# PCF8547.net
KiCad netlist of a schematic drawn in Altium Designer
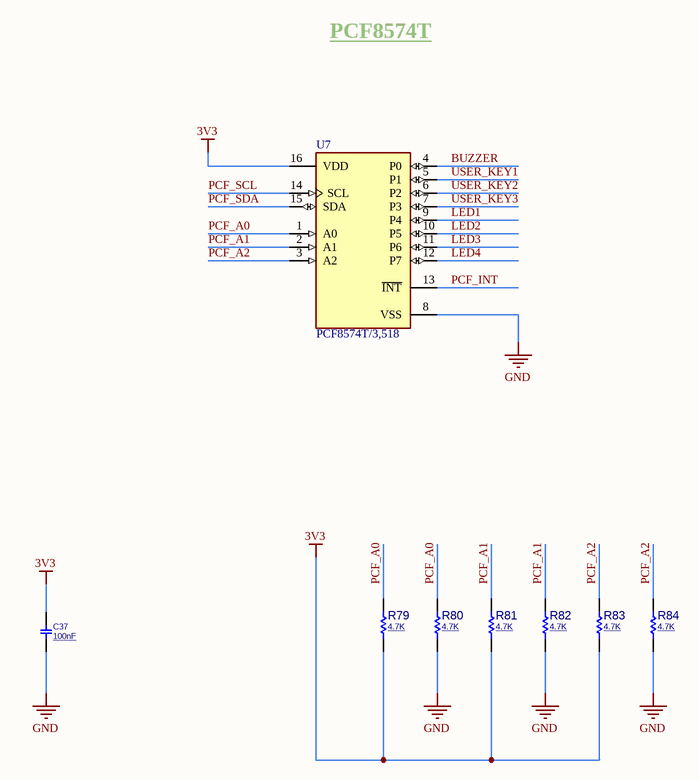
[diagram p0: PCF8547.SchDoc]

(export (version "E")
  (design (tool "Eeschema 10.0.6"))
  (components
    (comp (ref "C37")
      (value "100nF")
      (footprint "C0603")
      (description "CAP, MLCC, -F, -V, MATERIAL, -%, 0201")
      (fields (field (name "MANF_P#") "MANF_PART#"))
      (libsource (lib "passive_smd") (part "CAP_SMD_MLCC_0603"))
    )
    (comp (ref "R79")
      (value "4.7K")
      (footprint "R0603")
      (description "RESISTOR, SMD")
      (libsource (lib "passive_smd") (part "RES_SMD"))
    )
    (comp (ref "R80")
      (value "4.7K")
      (footprint "R0603")
      (description "RESISTOR, SMD")
      (libsource (lib "passive_smd") (part "RES_SMD"))
    )
    (comp (ref "R81")
      (value "4.7K")
      (footprint "R0603")
      (description "RESISTOR, SMD")
      (libsource (lib "passive_smd") (part "RES_SMD"))
    )
    (comp (ref "R82")
      (value "4.7K")
      (footprint "R0603")
      (description "RESISTOR, SMD")
      (libsource (lib "passive_smd") (part "RES_SMD"))
    )
    (comp (ref "R83")
      (value "4.7K")
      (footprint "R0603")
      (description "RESISTOR, SMD")
      (libsource (lib "passive_smd") (part "RES_SMD"))
    )
    (comp (ref "R84")
      (value "4.7K")
      (footprint "R0603")
      (description "RESISTOR, SMD")
      (libsource (lib "passive_smd") (part "RES_SMD"))
    )
    (comp (ref "U7")
      (value "PCF8574T/3,518")
      (footprint "FP-SOT162-1-MFG")
      (description "IC I/O EXPANDER I2C 8B 16SOIC")
      (fields
        (field (name "MANUFACTURER") "NXP Semiconductors")
        (field (name "OCTOPART") "https://octopart.com/pcf8574t%2F3%2C518-nxp+semiconductors-10470852")
      )
      (libsource (lib "PCF8574T") (part "PCF8574T"))
    )
  )
  (nets
    (net (code "1") (name "/BUZZER") (class "Default")
      (node (ref "U7") (pin "4") (pinfunction "P0_4") (pintype "bidirectional"))
    )
    (net (code "2") (name "/LED1") (class "Default")
      (node (ref "U7") (pin "9") (pinfunction "P4_9") (pintype "bidirectional"))
    )
    (net (code "3") (name "/LED2") (class "Default")
      (node (ref "U7") (pin "10") (pinfunction "P5_10") (pintype "bidirectional"))
    )
    (net (code "4") (name "/LED3") (class "Default")
      (node (ref "U7") (pin "11") (pinfunction "P6_11") (pintype "bidirectional"))
    )
    (net (code "5") (name "/LED4") (class "Default")
      (node (ref "U7") (pin "12") (pinfunction "P7_12") (pintype "bidirectional"))
    )
    (net (code "6") (name "/PCF_A0") (class "Default")
      (node (ref "R79") (pin "1") (pinfunction "1_1") (pintype "passive"))
      (node (ref "R80") (pin "1") (pinfunction "1_1") (pintype "passive"))
      (node (ref "U7") (pin "1") (pinfunction "A0_1") (pintype "input"))
    )
    (net (code "7") (name "/PCF_A1") (class "Default")
      (node (ref "R81") (pin "1") (pinfunction "1_1") (pintype "passive"))
      (node (ref "R82") (pin "1") (pinfunction "1_1") (pintype "passive"))
      (node (ref "U7") (pin "2") (pinfunction "A1_2") (pintype "input"))
    )
    (net (code "8") (name "/PCF_A2") (class "Default")
      (node (ref "R83") (pin "1") (pinfunction "1_1") (pintype "passive"))
      (node (ref "R84") (pin "1") (pinfunction "1_1") (pintype "passive"))
      (node (ref "U7") (pin "3") (pinfunction "A2_3") (pintype "input"))
    )
    (net (code "9") (name "/PCF_INT") (class "Default")
      (node (ref "U7") (pin "13") (pinfunction "~{INT}_13") (pintype "open_collector"))
    )
    (net (code "10") (name "/PCF_SCL") (class "Default")
      (node (ref "U7") (pin "14") (pinfunction "SCL_14") (pintype "input"))
    )
    (net (code "11") (name "/PCF_SDA") (class "Default")
      (node (ref "U7") (pin "15") (pinfunction "SDA_15") (pintype "bidirectional"))
    )
    (net (code "12") (name "/USER_KEY1") (class "Default")
      (node (ref "U7") (pin "5") (pinfunction "P1_5") (pintype "bidirectional"))
    )
    (net (code "13") (name "/USER_KEY2") (class "Default")
      (node (ref "U7") (pin "6") (pinfunction "P2_6") (pintype "bidirectional"))
    )
    (net (code "14") (name "/USER_KEY3") (class "Default")
      (node (ref "U7") (pin "7") (pinfunction "P3_7") (pintype "bidirectional"))
    )
    (net (code "15") (name "3V3") (class "Default")
      (node (ref "C37") (pin "2") (pinfunction "2_2") (pintype "passive"))
      (node (ref "R79") (pin "2") (pinfunction "2_2") (pintype "passive"))
      (node (ref "R81") (pin "2") (pinfunction "2_2") (pintype "passive"))
      (node (ref "R83") (pin "2") (pinfunction "2_2") (pintype "passive"))
      (node (ref "U7") (pin "16") (pinfunction "VDD_16") (pintype "power_in"))
    )
    (net (code "16") (name "GND") (class "Default")
      (node (ref "C37") (pin "1") (pinfunction "1_1") (pintype "passive"))
      (node (ref "R80") (pin "2") (pinfunction "2_2") (pintype "passive"))
      (node (ref "R82") (pin "2") (pinfunction "2_2") (pintype "passive"))
      (node (ref "R84") (pin "2") (pinfunction "2_2") (pintype "passive"))
      (node (ref "U7") (pin "8") (pinfunction "VSS_8") (pintype "power_in"))
    )
  )
)
